# Striso_USB_hub.net
KiCad netlist of a schematic drawn in EasyEDA Pro
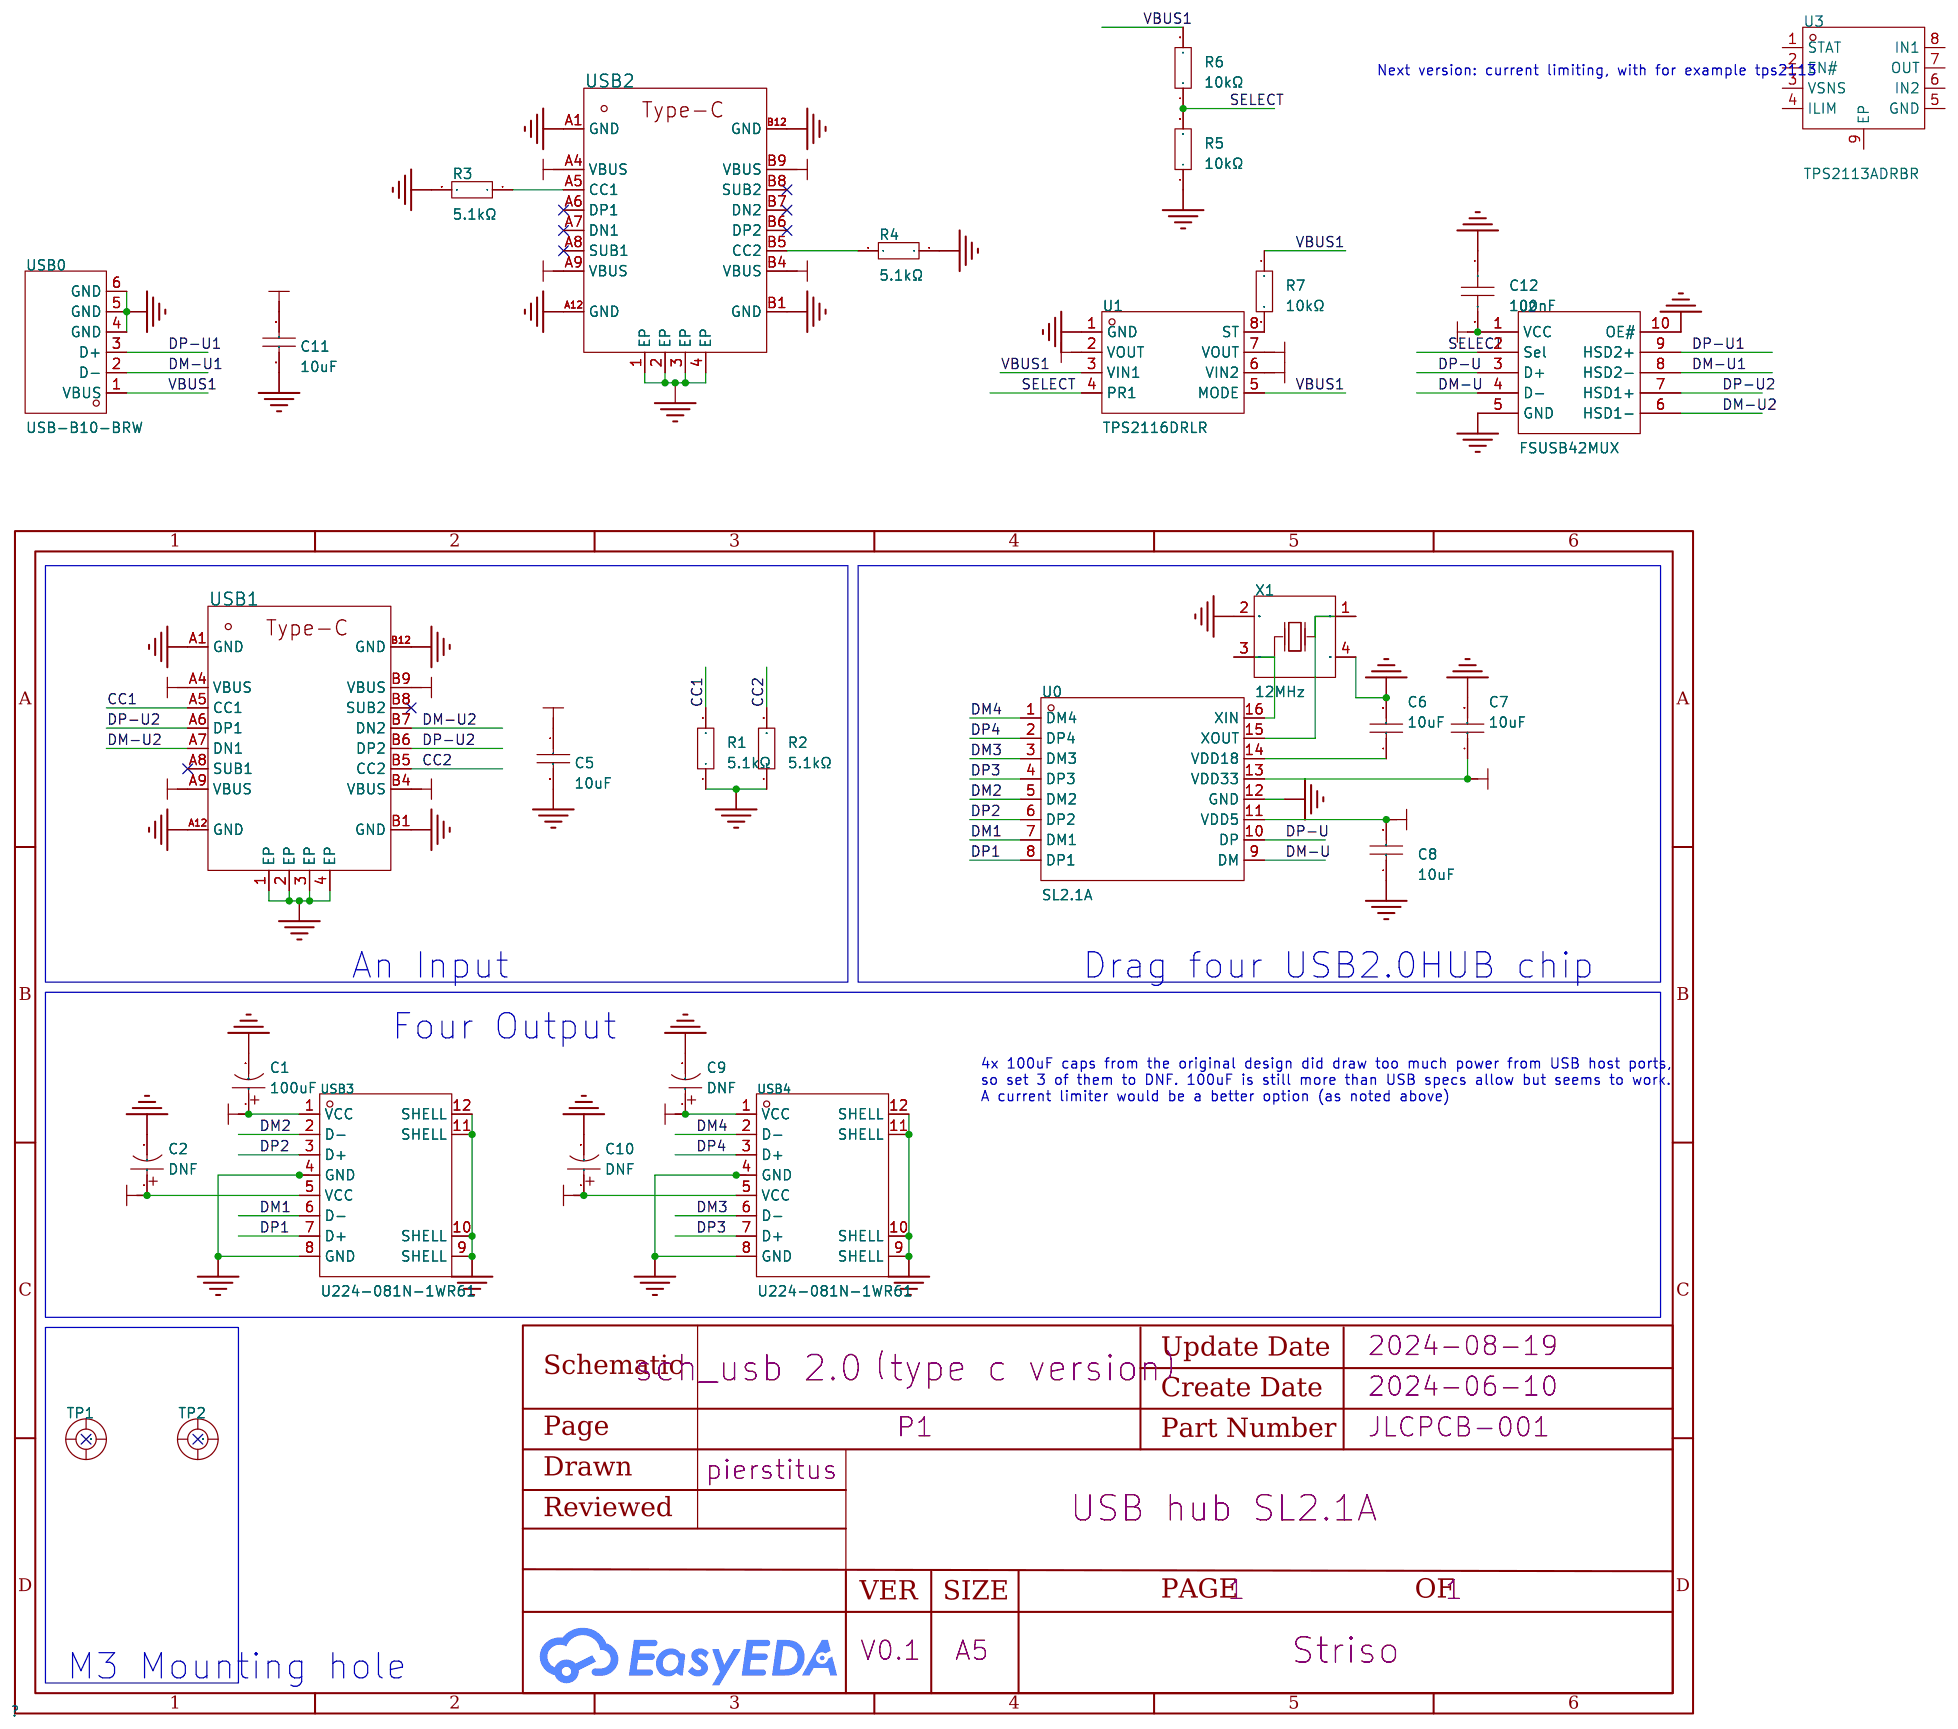
[diagram p0: schematic sheet]

(export (version "E")
  (design (tool "Eeschema 10.0.6"))
  (components
    (comp (ref "C1")
      (value "100uF")
      (footprint "easyedapro:CAP-SMD_BD6.3-L6.6-W6.6-FD")
      (description "容值:100uF;精度:±20%;额定电压:16V;纹波电流:129mA@10kHz;等效串联电阻:-;")
      (fields
        (field (name "Manufacturer Part") "UWX1C101MCL1GB")
        (field (name "Manufacturer") "Nichicon(尼吉康)")
      )
      (libsource (lib "easyedapro") (part "UWX1C101MCL1GB"))
    )
    (comp (ref "C2")
      (value "DNF")
      (footprint "easyedapro:CAP-SMD_BD6.3-L6.6-W6.6-FD")
      (description "容值:100uF;精度:±20%;额定电压:16V;纹波电流:129mA@10kHz;等效串联电阻:-;")
      (fields
        (field (name "Manufacturer Part") "UWX1C101MCL1GB")
        (field (name "Manufacturer") "Nichicon(尼吉康)")
      )
      (libsource (lib "easyedapro") (part "UWX1C101MCL1GB"))
    )
    (comp (ref "C5")
      (value "10uF")
      (footprint "easyedapro:C0805")
      (description "容值:10uF;精度:±10%;额定电压:25V;材质(温度系数):X5R;")
      (fields
        (field (name "Manufacturer Part") "CL21A106KAYNNNE")
        (field (name "Manufacturer") "SAMSUNG(三星)")
      )
      (libsource (lib "easyedapro") (part "CL21A106KAYNNNE"))
    )
    (comp (ref "C6")
      (value "10uF")
      (footprint "easyedapro:C0805")
      (description "容值:10uF;精度:±10%;额定电压:25V;材质(温度系数):X5R;")
      (fields
        (field (name "Manufacturer Part") "CL21A106KAYNNNE")
        (field (name "Manufacturer") "SAMSUNG(三星)")
      )
      (libsource (lib "easyedapro") (part "CL21A106KAYNNNE"))
    )
    (comp (ref "C7")
      (value "10uF")
      (footprint "easyedapro:C0805")
      (description "容值:10uF;精度:±10%;额定电压:25V;材质(温度系数):X5R;")
      (fields
        (field (name "Manufacturer Part") "CL21A106KAYNNNE")
        (field (name "Manufacturer") "SAMSUNG(三星)")
      )
      (libsource (lib "easyedapro") (part "CL21A106KAYNNNE"))
    )
    (comp (ref "C8")
      (value "10uF")
      (footprint "easyedapro:C0805")
      (description "容值:10uF;精度:±10%;额定电压:25V;材质(温度系数):X5R;")
      (fields
        (field (name "Manufacturer Part") "CL21A106KAYNNNE")
        (field (name "Manufacturer") "SAMSUNG(三星)")
      )
      (libsource (lib "easyedapro") (part "CL21A106KAYNNNE"))
    )
    (comp (ref "C9")
      (value "DNF")
      (footprint "easyedapro:CAP-SMD_BD6.3-L6.6-W6.6-FD")
      (description "容值:100uF;精度:±20%;额定电压:16V;纹波电流:129mA@10kHz;等效串联电阻:-;")
      (fields
        (field (name "Manufacturer Part") "UWX1C101MCL1GB")
        (field (name "Manufacturer") "Nichicon(尼吉康)")
      )
      (libsource (lib "easyedapro") (part "UWX1C101MCL1GB"))
    )
    (comp (ref "C10")
      (value "DNF")
      (footprint "easyedapro:CAP-SMD_BD6.3-L6.6-W6.6-FD")
      (description "容值:100uF;精度:±20%;额定电压:16V;纹波电流:129mA@10kHz;等效串联电阻:-;")
      (fields
        (field (name "Manufacturer Part") "UWX1C101MCL1GB")
        (field (name "Manufacturer") "Nichicon(尼吉康)")
      )
      (libsource (lib "easyedapro") (part "UWX1C101MCL1GB"))
    )
    (comp (ref "C11")
      (value "10uF")
      (footprint "easyedapro:C0805")
      (description "容值:10uF;精度:±10%;额定电压:25V;材质(温度系数):X5R;")
      (fields
        (field (name "Manufacturer Part") "CL21A106KAYNNNE")
        (field (name "Manufacturer") "SAMSUNG(三星)")
      )
      (libsource (lib "easyedapro") (part "CL21A106KAYNNNE"))
    )
    (comp (ref "C12")
      (value "100nF")
      (footprint "easyedapro:C0603")
      (libsource (lib "easyedapro") (part "CAP"))
    )
    (comp (ref "R1")
      (value "5.1kΩ")
      (footprint "easyedapro:R0201")
      (libsource (lib "easyedapro") (part "Res"))
    )
    (comp (ref "R2")
      (value "5.1kΩ")
      (footprint "easyedapro:R0201")
      (libsource (lib "easyedapro") (part "Res"))
    )
    (comp (ref "R3")
      (value "5.1kΩ")
      (footprint "easyedapro:R0201")
      (libsource (lib "easyedapro") (part "Res"))
    )
    (comp (ref "R4")
      (value "5.1kΩ")
      (footprint "easyedapro:R0201")
      (libsource (lib "easyedapro") (part "Res"))
    )
    (comp (ref "R5")
      (value "10kΩ")
      (footprint "easyedapro:R0201")
      (libsource (lib "easyedapro") (part "Res"))
    )
    (comp (ref "R6")
      (value "10kΩ")
      (footprint "easyedapro:R0201")
      (libsource (lib "easyedapro") (part "Res"))
    )
    (comp (ref "R7")
      (value "10kΩ")
      (footprint "easyedapro:R0201")
      (libsource (lib "easyedapro") (part "Res"))
    )
    (comp (ref "TP1")
      (value "~")
      (footprint "easyedapro:M3")
      (fields (field (name "Manufacturer Part") "M3x10+6") (field (name "Manufacturer") "Shuntian(顺天五金)"))
      (libsource (lib "easyedapro") (part "M3"))
    )
    (comp (ref "TP2")
      (value "~")
      (footprint "easyedapro:M3")
      (fields (field (name "Manufacturer Part") "M3x10+6") (field (name "Manufacturer") "Shuntian(顺天五金)"))
      (libsource (lib "easyedapro") (part "M3"))
    )
    (comp (ref "U0")
      (value "SL2.1A")
      (footprint "easyedapro:SOP-16_L10.0-W3.9-P1.27-LS6.0-BL")
      (description "应用功能:集线器;接口协议:-;")
      (fields (field (name "Manufacturer") "CoreChips(和芯润德)"))
      (libsource (lib "easyedapro") (part "SL2.1A"))
    )
    (comp (ref "U1")
      (value "TPS2116DRLR")
      (footprint "easyedapro:SOT-583-8_L2.1-W1.6-P0.50-LS1.6-BL")
      (fields (field (name "Manufacturer") "TI(德州仪器)"))
      (libsource (lib "easyedapro") (part "TPS2116DRLR"))
    )
    (comp (ref "U2")
      (value "FSUSB42MUX")
      (footprint "easyedapro:MSOP-10_L3.0-W3.0-P0.50-LS5.0-BL")
      (description "Supply Voltage:2.4V~4.4V Supply Voltage:2.4V~4.4V On-State Resistance (Max):6.5Ω")
      (fields (field (name "Manufacturer") "onsemi(安森美)"))
      (libsource (lib "easyedapro") (part "FSUSB42MUX"))
    )
    (comp (ref "U3")
      (value "TPS2113ADRBR")
      (footprint "easyedapro:SON-8_L3.0-W3.0-P0.65-LS3.0-BL-EP")
      (fields (field (name "Manufacturer") "TI(德州仪器)"))
      (libsource (lib "easyedapro") (part "TPS2113ADRBR"))
    )
    (comp (ref "USB0")
      (value "USB-B10-BRW")
      (footprint "easyedapro:USB-B-TH_USB-B10-BRW")
      (fields (field (name "Manufacturer") "XUNPU(讯普)"))
      (libsource (lib "easyedapro") (part "USB-B10-BRW"))
    )
    (comp (ref "USB1")
      (value "KH-TYPE-C-16P")
      (footprint "easyedapro:USB-C-SMD_KH-TYPE-C-16P")
      (description "Type-C母座 16PIN 立式四角贴板无压片")
      (fields (field (name "Manufacturer") "kinghelm(金航标)"))
      (libsource (lib "easyedapro") (part "KH-TYPE-C-16P"))
    )
    (comp (ref "USB2")
      (value "KH-TYPE-C-16P")
      (footprint "easyedapro:USB-C-SMD_KH-TYPE-C-16P")
      (description "Type-C母座 16PIN 立式四角贴板无压片")
      (fields (field (name "Manufacturer") "kinghelm(金航标)"))
      (libsource (lib "easyedapro") (part "KH-TYPE-C-16P"))
    )
    (comp (ref "USB3")
      (value "U224-081N-1WR61")
      (footprint "easyedapro:USB-A-TH_XKB_U224-08XN-1XR61")
      (fields (field (name "Manufacturer") "XKB Connectivity(中国星坤)"))
      (libsource (lib "easyedapro") (part "U224-081N-1WR61"))
    )
    (comp (ref "USB4")
      (value "U224-081N-1WR61")
      (footprint "easyedapro:USB-A-TH_XKB_U224-08XN-1XR61")
      (fields (field (name "Manufacturer") "XKB Connectivity(中国星坤)"))
      (libsource (lib "easyedapro") (part "U224-081N-1WR61"))
    )
    (comp (ref "X1")
      (value "12MHz")
      (footprint "easyedapro:OSC-SMD_4P-L3.2-W2.5-BL")
      (fields (field (name "Manufacturer Part") "X322512MSB4SI") (field (name "Manufacturer") "YXC(扬兴晶振)"))
      (libsource (lib "easyedapro") (part "X322512MSB4SI"))
    )
  )
  (nets
    (net (code "1") (name "/CC1") (class "Default")
      (node (ref "R1") (pin "2") (pinfunction "2_2") (pintype "input"))
      (node (ref "USB1") (pin "A5") (pinfunction "CC1_A5") (pintype "input"))
    )
    (net (code "2") (name "/CC2") (class "Default")
      (node (ref "R2") (pin "2") (pinfunction "2_2") (pintype "input"))
      (node (ref "USB1") (pin "B5") (pinfunction "CC2_B5") (pintype "input"))
    )
    (net (code "3") (name "/DM-U") (class "Default")
      (node (ref "U0") (pin "9") (pinfunction "DM_9") (pintype "input"))
      (node (ref "U2") (pin "4") (pinfunction "D-_4") (pintype "input"))
    )
    (net (code "4") (name "/DM-U1") (class "Default")
      (node (ref "U2") (pin "8") (pinfunction "HSD2-_8") (pintype "input"))
      (node (ref "USB0") (pin "2") (pinfunction "D-_2") (pintype "unspecified"))
    )
    (net (code "5") (name "/DM-U2") (class "Default")
      (node (ref "U2") (pin "6") (pinfunction "HSD1-_6") (pintype "input"))
      (node (ref "USB1") (pin "A7") (pinfunction "DN1_A7") (pintype "input"))
      (node (ref "USB1") (pin "B7") (pinfunction "DN2_B7") (pintype "input"))
    )
    (net (code "6") (name "/DM1") (class "Default")
      (node (ref "U0") (pin "7") (pinfunction "DM1_7") (pintype "input"))
      (node (ref "USB3") (pin "6") (pinfunction "D-_6") (pintype "input"))
    )
    (net (code "7") (name "/DM2") (class "Default")
      (node (ref "U0") (pin "5") (pinfunction "DM2_5") (pintype "input"))
      (node (ref "USB3") (pin "2") (pinfunction "D-_2") (pintype "input"))
    )
    (net (code "8") (name "/DM3") (class "Default")
      (node (ref "U0") (pin "3") (pinfunction "DM3_3") (pintype "input"))
      (node (ref "USB4") (pin "6") (pinfunction "D-_6") (pintype "input"))
    )
    (net (code "9") (name "/DM4") (class "Default")
      (node (ref "U0") (pin "1") (pinfunction "DM4_1") (pintype "input"))
      (node (ref "USB4") (pin "2") (pinfunction "D-_2") (pintype "input"))
    )
    (net (code "10") (name "/DP-U") (class "Default")
      (node (ref "U0") (pin "10") (pinfunction "DP_10") (pintype "input"))
      (node (ref "U2") (pin "3") (pinfunction "D+_3") (pintype "input"))
    )
    (net (code "11") (name "/DP-U1") (class "Default")
      (node (ref "U2") (pin "9") (pinfunction "HSD2+_9") (pintype "input"))
      (node (ref "USB0") (pin "3") (pinfunction "D+_3") (pintype "unspecified"))
    )
    (net (code "12") (name "/DP-U2") (class "Default")
      (node (ref "U2") (pin "7") (pinfunction "HSD1+_7") (pintype "input"))
      (node (ref "USB1") (pin "A6") (pinfunction "DP1_A6") (pintype "input"))
      (node (ref "USB1") (pin "B6") (pinfunction "DP2_B6") (pintype "input"))
    )
    (net (code "13") (name "/DP1") (class "Default")
      (node (ref "U0") (pin "8") (pinfunction "DP1_8") (pintype "input"))
      (node (ref "USB3") (pin "7") (pinfunction "D+_7") (pintype "input"))
    )
    (net (code "14") (name "/DP2") (class "Default")
      (node (ref "U0") (pin "6") (pinfunction "DP2_6") (pintype "input"))
      (node (ref "USB3") (pin "3") (pinfunction "D+_3") (pintype "input"))
    )
    (net (code "15") (name "/DP3") (class "Default")
      (node (ref "U0") (pin "4") (pinfunction "DP3_4") (pintype "input"))
      (node (ref "USB4") (pin "7") (pinfunction "D+_7") (pintype "input"))
    )
    (net (code "16") (name "/DP4") (class "Default")
      (node (ref "U0") (pin "2") (pinfunction "DP4_2") (pintype "input"))
      (node (ref "USB4") (pin "3") (pinfunction "D+_3") (pintype "input"))
    )
    (net (code "17") (name "/SELECT") (class "Default")
      (node (ref "R5") (pin "2") (pinfunction "2_2") (pintype "input"))
      (node (ref "R6") (pin "1") (pinfunction "1_1") (pintype "input"))
      (node (ref "U1") (pin "4") (pinfunction "PR1_4") (pintype "unspecified"))
      (node (ref "U2") (pin "2") (pinfunction "Sel_2") (pintype "input"))
    )
    (net (code "18") (name "3.3V") (class "Default")
      (node (ref "C12") (pin "2") (pinfunction "2_2") (pintype "input"))
      (node (ref "C7") (pin "1") (pinfunction "1_1") (pintype "input"))
      (node (ref "U0") (pin "13") (pinfunction "VDD33_13") (pintype "input"))
      (node (ref "U2") (pin "1") (pinfunction "VCC_1") (pintype "input"))
    )
    (net (code "19") (name "GND") (class "Default")
      (node (ref "C1") (pin "2") (pinfunction "2_2") (pintype "input"))
      (node (ref "C10") (pin "2") (pinfunction "2_2") (pintype "input"))
      (node (ref "C11") (pin "2") (pinfunction "2_2") (pintype "input"))
      (node (ref "C12") (pin "1") (pinfunction "1_1") (pintype "input"))
      (node (ref "C2") (pin "2") (pinfunction "2_2") (pintype "input"))
      (node (ref "C5") (pin "2") (pinfunction "2_2") (pintype "input"))
      (node (ref "C6") (pin "2") (pinfunction "2_2") (pintype "input"))
      (node (ref "C7") (pin "2") (pinfunction "2_2") (pintype "input"))
      (node (ref "C8") (pin "1") (pinfunction "1_1") (pintype "input"))
      (node (ref "C9") (pin "2") (pinfunction "2_2") (pintype "input"))
      (node (ref "R1") (pin "1") (pinfunction "1_1") (pintype "input"))
      (node (ref "R2") (pin "1") (pinfunction "1_1") (pintype "input"))
      (node (ref "R3") (pin "2") (pinfunction "2_2") (pintype "input"))
      (node (ref "R4") (pin "1") (pinfunction "1_1") (pintype "input"))
      (node (ref "R5") (pin "1") (pinfunction "1_1") (pintype "input"))
      (node (ref "U0") (pin "12") (pinfunction "GND_12") (pintype "input"))
      (node (ref "U1") (pin "1") (pinfunction "GND_1") (pintype "unspecified"))
      (node (ref "U2") (pin "10") (pinfunction "OE#_10") (pintype "input"))
      (node (ref "U2") (pin "5") (pinfunction "GND_5") (pintype "input"))
      (node (ref "USB0") (pin "4") (pinfunction "GND_4") (pintype "unspecified"))
      (node (ref "USB0") (pin "5") (pinfunction "GND_5") (pintype "unspecified"))
      (node (ref "USB0") (pin "6") (pinfunction "GND_6") (pintype "unspecified"))
      (node (ref "USB1") (pin "1") (pinfunction "EP_1") (pintype "input"))
      (node (ref "USB1") (pin "2") (pinfunction "EP_2") (pintype "input"))
      (node (ref "USB1") (pin "3") (pinfunction "EP_3") (pintype "input"))
      (node (ref "USB1") (pin "4") (pinfunction "EP_4") (pintype "input"))
      (node (ref "USB1") (pin "A1") (pinfunction "GND_A1") (pintype "input"))
      (node (ref "USB1") (pin "A12") (pinfunction "GND_A12") (pintype "input"))
      (node (ref "USB1") (pin "B1") (pinfunction "GND_B1") (pintype "input"))
      (node (ref "USB1") (pin "B12") (pinfunction "GND_B12") (pintype "input"))
      (node (ref "USB2") (pin "1") (pinfunction "EP_1") (pintype "input"))
      (node (ref "USB2") (pin "2") (pinfunction "EP_2") (pintype "input"))
      (node (ref "USB2") (pin "3") (pinfunction "EP_3") (pintype "input"))
      (node (ref "USB2") (pin "4") (pinfunction "EP_4") (pintype "input"))
      (node (ref "USB2") (pin "A1") (pinfunction "GND_A1") (pintype "input"))
      (node (ref "USB2") (pin "A12") (pinfunction "GND_A12") (pintype "input"))
      (node (ref "USB2") (pin "B1") (pinfunction "GND_B1") (pintype "input"))
      (node (ref "USB2") (pin "B12") (pinfunction "GND_B12") (pintype "input"))
      (node (ref "USB3") (pin "10") (pinfunction "SHELL_10") (pintype "input"))
      (node (ref "USB3") (pin "11") (pinfunction "SHELL_11") (pintype "input"))
      (node (ref "USB3") (pin "12") (pinfunction "SHELL_12") (pintype "input"))
      (node (ref "USB3") (pin "4") (pinfunction "GND_4") (pintype "input"))
      (node (ref "USB3") (pin "8") (pinfunction "GND_8") (pintype "input"))
      (node (ref "USB3") (pin "9") (pinfunction "SHELL_9") (pintype "input"))
      (node (ref "USB4") (pin "10") (pinfunction "SHELL_10") (pintype "input"))
      (node (ref "USB4") (pin "11") (pinfunction "SHELL_11") (pintype "input"))
      (node (ref "USB4") (pin "12") (pinfunction "SHELL_12") (pintype "input"))
      (node (ref "USB4") (pin "4") (pinfunction "GND_4") (pintype "input"))
      (node (ref "USB4") (pin "8") (pinfunction "GND_8") (pintype "input"))
      (node (ref "USB4") (pin "9") (pinfunction "SHELL_9") (pintype "input"))
      (node (ref "X1") (pin "2") (pinfunction "GND_2") (pintype "unspecified"))
      (node (ref "X1") (pin "4") (pinfunction "GND_4") (pintype "unspecified"))
    )
    (net (code "20") (name "Net-(U0-VDD18)") (class "Default")
      (node (ref "C6") (pin "1") (pinfunction "1_1") (pintype "input"))
      (node (ref "U0") (pin "14") (pinfunction "VDD18_14") (pintype "input"))
    )
    (net (code "21") (name "Net-(U0-XIN)") (class "Default")
      (node (ref "U0") (pin "16") (pinfunction "XIN_16") (pintype "input"))
      (node (ref "X1") (pin "3") (pinfunction "OSC2_3") (pintype "unspecified"))
    )
    (net (code "22") (name "Net-(U0-XOUT)") (class "Default")
      (node (ref "U0") (pin "15") (pinfunction "XOUT_15") (pintype "input"))
      (node (ref "X1") (pin "1") (pinfunction "OSC1_1") (pintype "unspecified"))
    )
    (net (code "23") (name "Net-(U1-ST)") (class "Default")
      (node (ref "R7") (pin "2") (pinfunction "2_2") (pintype "input"))
      (node (ref "U1") (pin "8") (pinfunction "ST_8") (pintype "unspecified"))
    )
    (net (code "24") (name "Net-(USB2-CC1)") (class "Default")
      (node (ref "R3") (pin "1") (pinfunction "1_1") (pintype "input"))
      (node (ref "USB2") (pin "A5") (pinfunction "CC1_A5") (pintype "input"))
    )
    (net (code "25") (name "Net-(USB2-CC2)") (class "Default")
      (node (ref "R4") (pin "2") (pinfunction "2_2") (pintype "input"))
      (node (ref "USB2") (pin "B5") (pinfunction "CC2_B5") (pintype "input"))
    )
    (net (code "26") (name "VBUS") (class "Default")
      (node (ref "C1") (pin "1") (pinfunction "1_1") (pintype "input"))
      (node (ref "C10") (pin "1") (pinfunction "1_1") (pintype "input"))
      (node (ref "C2") (pin "1") (pinfunction "1_1") (pintype "input"))
      (node (ref "C8") (pin "2") (pinfunction "2_2") (pintype "input"))
      (node (ref "C9") (pin "1") (pinfunction "1_1") (pintype "input"))
      (node (ref "U0") (pin "11") (pinfunction "VDD5_11") (pintype "input"))
      (node (ref "U1") (pin "2") (pinfunction "VOUT_2") (pintype "unspecified"))
      (node (ref "U1") (pin "7") (pinfunction "VOUT_7") (pintype "unspecified"))
      (node (ref "USB2") (pin "A4") (pinfunction "VBUS_A4") (pintype "input"))
      (node (ref "USB2") (pin "A9") (pinfunction "VBUS_A9") (pintype "input"))
      (node (ref "USB2") (pin "B4") (pinfunction "VBUS_B4") (pintype "input"))
      (node (ref "USB2") (pin "B9") (pinfunction "VBUS_B9") (pintype "input"))
      (node (ref "USB3") (pin "1") (pinfunction "VCC_1") (pintype "input"))
      (node (ref "USB3") (pin "5") (pinfunction "VCC_5") (pintype "input"))
      (node (ref "USB4") (pin "1") (pinfunction "VCC_1") (pintype "input"))
      (node (ref "USB4") (pin "5") (pinfunction "VCC_5") (pintype "input"))
    )
    (net (code "27") (name "VBUS1") (class "Default")
      (node (ref "C11") (pin "1") (pinfunction "1_1") (pintype "input"))
      (node (ref "R6") (pin "2") (pinfunction "2_2") (pintype "input"))
      (node (ref "R7") (pin "1") (pinfunction "1_1") (pintype "input"))
      (node (ref "U1") (pin "3") (pinfunction "VIN1_3") (pintype "unspecified"))
      (node (ref "U1") (pin "5") (pinfunction "MODE_5") (pintype "unspecified"))
      (node (ref "USB0") (pin "1") (pinfunction "VBUS_1") (pintype "unspecified"))
    )
    (net (code "28") (name "VBUS2") (class "Default")
      (node (ref "C5") (pin "1") (pinfunction "1_1") (pintype "input"))
      (node (ref "U1") (pin "6") (pinfunction "VIN2_6") (pintype "unspecified"))
      (node (ref "USB1") (pin "A4") (pinfunction "VBUS_A4") (pintype "input"))
      (node (ref "USB1") (pin "A9") (pinfunction "VBUS_A9") (pintype "input"))
      (node (ref "USB1") (pin "B4") (pinfunction "VBUS_B4") (pintype "input"))
      (node (ref "USB1") (pin "B9") (pinfunction "VBUS_B9") (pintype "input"))
    )
    (net (code "29") (name "unconnected-(TP1-Pad0)") (class "Default")
      (node (ref "TP1") (pin "0") (pinfunction "0_0") (pintype "input+no_connect"))
    )
    (net (code "30") (name "unconnected-(TP2-Pad0)") (class "Default")
      (node (ref "TP2") (pin "0") (pinfunction "0_0") (pintype "input+no_connect"))
    )
    (net (code "31") (name "unconnected-(U3-EN#-Pad2)") (class "Default")
      (node (ref "U3") (pin "2") (pinfunction "EN#_2") (pintype "input"))
    )
    (net (code "32") (name "unconnected-(U3-EP-Pad9)") (class "Default")
      (node (ref "U3") (pin "9") (pinfunction "EP_9") (pintype "input"))
    )
    (net (code "33") (name "unconnected-(U3-GND-Pad5)") (class "Default")
      (node (ref "U3") (pin "5") (pinfunction "GND_5") (pintype "input"))
    )
    (net (code "34") (name "unconnected-(U3-ILIM-Pad4)") (class "Default")
      (node (ref "U3") (pin "4") (pinfunction "ILIM_4") (pintype "input"))
    )
    (net (code "35") (name "unconnected-(U3-IN1-Pad8)") (class "Default")
      (node (ref "U3") (pin "8") (pinfunction "IN1_8") (pintype "input"))
    )
    (net (code "36") (name "unconnected-(U3-IN2-Pad6)") (class "Default")
      (node (ref "U3") (pin "6") (pinfunction "IN2_6") (pintype "input"))
    )
    (net (code "37") (name "unconnected-(U3-OUT-Pad7)") (class "Default")
      (node (ref "U3") (pin "7") (pinfunction "OUT_7") (pintype "input"))
    )
    (net (code "38") (name "unconnected-(U3-STAT-Pad1)") (class "Default")
      (node (ref "U3") (pin "1") (pinfunction "STAT_1") (pintype "input"))
    )
    (net (code "39") (name "unconnected-(U3-VSNS-Pad3)") (class "Default")
      (node (ref "U3") (pin "3") (pinfunction "VSNS_3") (pintype "input"))
    )
    (net (code "40") (name "unconnected-(USB1-SUB1-PadA8)") (class "Default")
      (node (ref "USB1") (pin "A8") (pinfunction "SUB1_A8") (pintype "input+no_connect"))
    )
    (net (code "41") (name "unconnected-(USB1-SUB2-PadB8)") (class "Default")
      (node (ref "USB1") (pin "B8") (pinfunction "SUB2_B8") (pintype "input+no_connect"))
    )
    (net (code "42") (name "unconnected-(USB2-DN1-PadA7)") (class "Default")
      (node (ref "USB2") (pin "A7") (pinfunction "DN1_A7") (pintype "input+no_connect"))
    )
    (net (code "43") (name "unconnected-(USB2-DN2-PadB7)") (class "Default")
      (node (ref "USB2") (pin "B7") (pinfunction "DN2_B7") (pintype "input+no_connect"))
    )
    (net (code "44") (name "unconnected-(USB2-DP1-PadA6)") (class "Default")
      (node (ref "USB2") (pin "A6") (pinfunction "DP1_A6") (pintype "input+no_connect"))
    )
    (net (code "45") (name "unconnected-(USB2-DP2-PadB6)") (class "Default")
      (node (ref "USB2") (pin "B6") (pinfunction "DP2_B6") (pintype "input+no_connect"))
    )
    (net (code "46") (name "unconnected-(USB2-SUB1-PadA8)") (class "Default")
      (node (ref "USB2") (pin "A8") (pinfunction "SUB1_A8") (pintype "input+no_connect"))
    )
    (net (code "47") (name "unconnected-(USB2-SUB2-PadB8)") (class "Default")
      (node (ref "USB2") (pin "B8") (pinfunction "SUB2_B8") (pintype "input+no_connect"))
    )
  )
)
